# Memory.net
KiCad netlist of a schematic drawn in Altium Designer
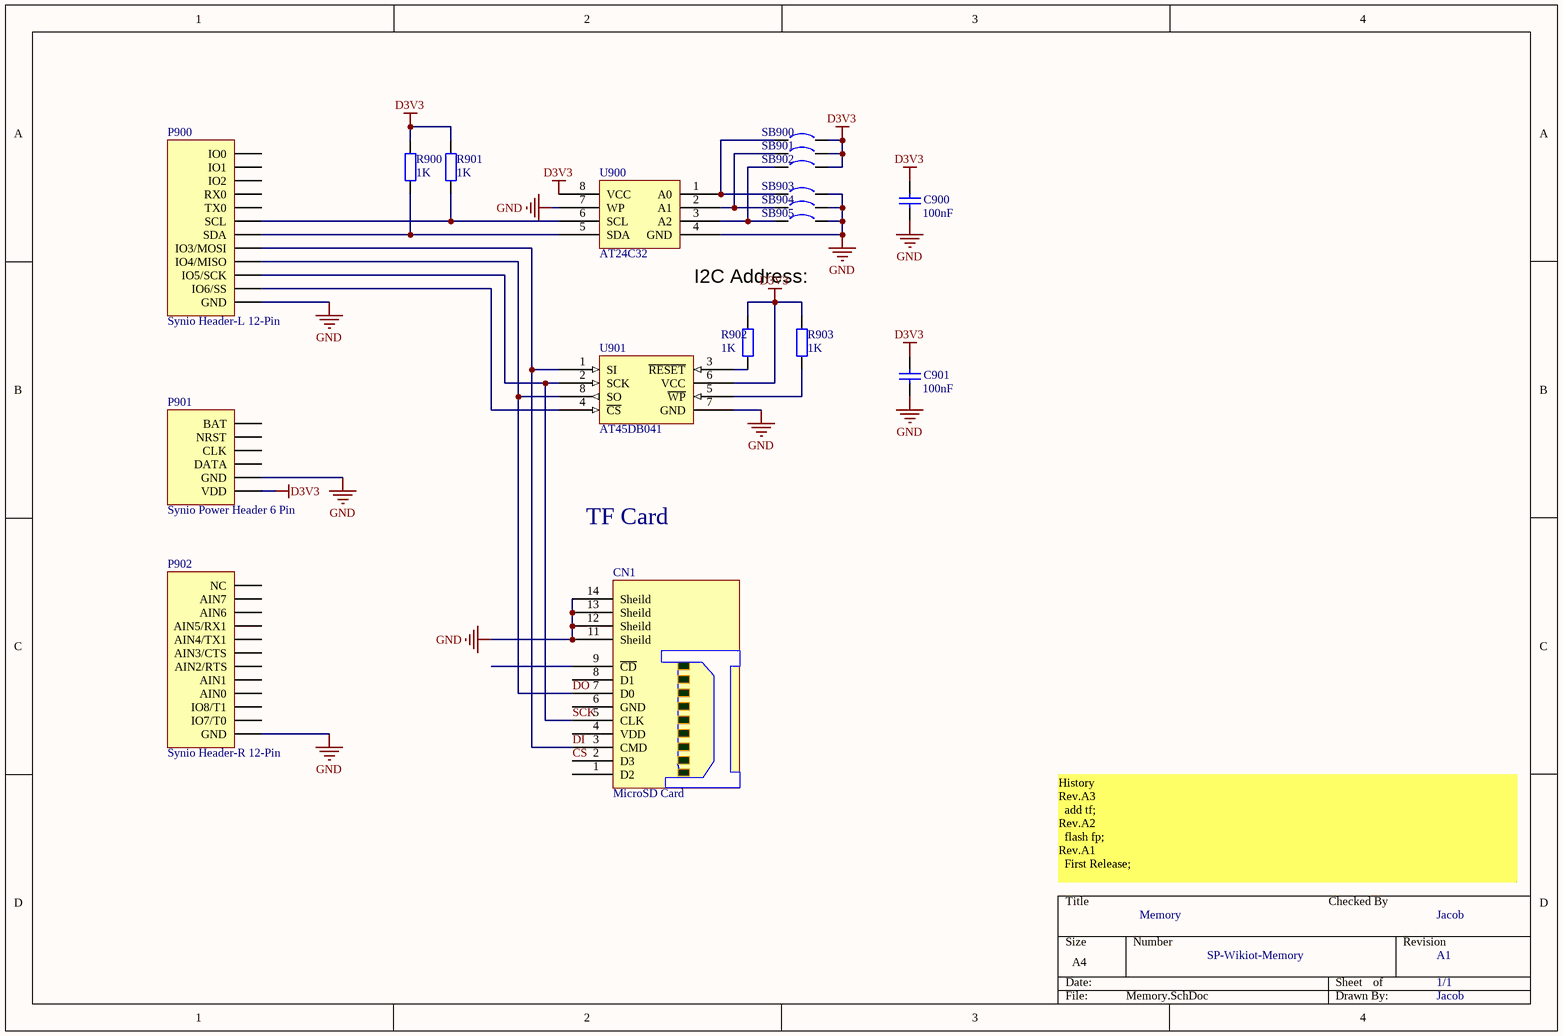
[diagram p0: Memory.SchDoc]

(export (version "E")
  (design (tool "Eeschema 10.0.6"))
  (components
    (comp (ref "C900")
      (value "100nF")
      (footprint "C0603L")
      (description "Capacitor")
      (fields (field (name "PUBLISHER") "Altium Limited"))
      (libsource (lib "Miscellaneous Devices") (part "Cap"))
    )
    (comp (ref "C901")
      (value "100nF")
      (footprint "C0603L")
      (description "Capacitor")
      (fields (field (name "PUBLISHER") "Altium Limited"))
      (libsource (lib "Miscellaneous Devices") (part "Cap"))
    )
    (comp (ref "CN1")
      (value "MicroSD Card")
      (footprint "MicroSD")
      (libsource (lib "Connector") (part "MicroSD Card"))
    )
    (comp (ref "P900")
      (value "Synio Header-L 12-Pin")
      (footprint "HDR1X12/2.54MM")
      (description "Synio Header-L, 12-Pin")
      (fields (field (name "PUBLISHER") "Altium Limited"))
      (libsource (lib "Connector") (part "Synio Header-L 12-Pin"))
    )
    (comp (ref "P901")
      (value "Synio Power Header 6 Pin")
      (footprint "HDR1X6/2.54MM")
      (libsource (lib "Connector") (part "Synio Power Header 6 Pin"))
    )
    (comp (ref "P902")
      (value "Synio Header-R 12-Pin")
      (footprint "HDR1X12/2.54MM")
      (description "Synio Header-R, 12-Pin")
      (fields (field (name "PUBLISHER") "Altium Limited"))
      (libsource (lib "Connector") (part "Synio Header-R 12-Pin"))
    )
    (comp (ref "R900")
      (value "1K")
      (footprint "R0603")
      (description "Resistor")
      (fields (field (name "PUBLISHER") "Altium Limited"))
      (libsource (lib "Miscellaneous Devices") (part "Res2"))
    )
    (comp (ref "R901")
      (value "1K")
      (footprint "R0603")
      (description "Resistor")
      (fields (field (name "PUBLISHER") "Altium Limited"))
      (libsource (lib "Miscellaneous Devices") (part "Res2"))
    )
    (comp (ref "R902")
      (value "1K")
      (footprint "R0603")
      (description "Resistor")
      (fields (field (name "PUBLISHER") "Altium Limited"))
      (libsource (lib "") (part "Res2_1"))
    )
    (comp (ref "R903")
      (value "1K")
      (footprint "R0603")
      (description "Resistor")
      (fields (field (name "PUBLISHER") "Altium Limited"))
      (libsource (lib "") (part "Res2_1"))
    )
    (comp (ref "SB900")
      (value "Circuit Breaker")
      (footprint "JP2_SMD")
      (fields (field (name "PUBLISHER") "Altium Limited"))
      (libsource (lib "Misc") (part "Circuit Breaker"))
    )
    (comp (ref "SB901")
      (value "Circuit Breaker")
      (footprint "JP2_SMD")
      (fields (field (name "PUBLISHER") "Altium Limited"))
      (libsource (lib "Misc") (part "Circuit Breaker"))
    )
    (comp (ref "SB902")
      (value "Circuit Breaker")
      (footprint "JP2_SMD")
      (fields (field (name "PUBLISHER") "Altium Limited"))
      (libsource (lib "Misc") (part "Circuit Breaker"))
    )
    (comp (ref "SB903")
      (value "Circuit Breaker")
      (footprint "JP2_SMD")
      (fields (field (name "PUBLISHER") "Altium Limited"))
      (libsource (lib "Misc") (part "Circuit Breaker"))
    )
    (comp (ref "SB904")
      (value "Circuit Breaker")
      (footprint "JP2_SMD")
      (fields (field (name "PUBLISHER") "Altium Limited"))
      (libsource (lib "Misc") (part "Circuit Breaker"))
    )
    (comp (ref "SB905")
      (value "Circuit Breaker")
      (footprint "JP2_SMD")
      (fields (field (name "PUBLISHER") "Altium Limited"))
      (libsource (lib "Misc") (part "Circuit Breaker"))
    )
    (comp (ref "U900")
      (value "AT24C32")
      (footprint "SO8W_M")
      (description "IIC EEPROM")
      (libsource (lib "Logic") (part "At24CXX"))
    )
    (comp (ref "U901")
      (value "AT45DB041")
      (footprint "SO8_N")
      (description "4M Serial Flash")
      (libsource (lib "Logic") (part "AT45DB041"))
    )
  )
  (nets
    (net (code "1") (name "/CS") (class "Default")
      (node (ref "CN1") (pin "2") (pinfunction "D3_2") (pintype "passive"))
    )
    (net (code "2") (name "/DI") (class "Default")
      (node (ref "CN1") (pin "3") (pinfunction "CMD_3") (pintype "passive"))
      (node (ref "P900") (pin "5") (pinfunction "IO3/MOSI_5") (pintype "passive"))
      (node (ref "U901") (pin "1") (pinfunction "SI_1") (pintype "input"))
    )
    (net (code "3") (name "/DO") (class "Default")
      (node (ref "CN1") (pin "7") (pinfunction "D0_7") (pintype "passive"))
      (node (ref "P900") (pin "4") (pinfunction "IO4/MISO_4") (pintype "passive"))
      (node (ref "U901") (pin "8") (pinfunction "SO_8") (pintype "output"))
    )
    (net (code "4") (name "/SCK") (class "Default")
      (node (ref "CN1") (pin "5") (pinfunction "CLK_5") (pintype "passive"))
      (node (ref "P900") (pin "3") (pinfunction "IO5/SCK_3") (pintype "passive"))
      (node (ref "U901") (pin "2") (pinfunction "SCK_2") (pintype "input"))
    )
    (net (code "5") (name "D3V3") (class "Default")
      (node (ref "C900") (pin "1") (pinfunction "1_1") (pintype "passive"))
      (node (ref "C901") (pin "1") (pinfunction "1_1") (pintype "passive"))
      (node (ref "P901") (pin "1") (pinfunction "VDD_1") (pintype "passive"))
      (node (ref "R900") (pin "2") (pinfunction "2_2") (pintype "passive"))
      (node (ref "R901") (pin "2") (pinfunction "2_2") (pintype "passive"))
      (node (ref "R902") (pin "1") (pinfunction "1_1") (pintype "passive"))
      (node (ref "R903") (pin "1") (pinfunction "1_1") (pintype "passive"))
      (node (ref "SB900") (pin "2") (pinfunction "2_2") (pintype "passive"))
      (node (ref "SB901") (pin "2") (pinfunction "2_2") (pintype "passive"))
      (node (ref "SB902") (pin "2") (pinfunction "2_2") (pintype "passive"))
      (node (ref "U900") (pin "8") (pinfunction "VCC_8") (pintype "passive"))
      (node (ref "U901") (pin "6") (pinfunction "VCC_6") (pintype "power_in"))
    )
    (net (code "6") (name "GND") (class "Default")
      (node (ref "C900") (pin "2") (pinfunction "2_2") (pintype "passive"))
      (node (ref "C901") (pin "2") (pinfunction "2_2") (pintype "passive"))
      (node (ref "CN1") (pin "11") (pinfunction "Sheild_11") (pintype "passive"))
      (node (ref "CN1") (pin "12") (pinfunction "Sheild_12") (pintype "passive"))
      (node (ref "CN1") (pin "13") (pinfunction "Sheild_13") (pintype "passive"))
      (node (ref "CN1") (pin "14") (pinfunction "Sheild_14") (pintype "passive"))
      (node (ref "P900") (pin "1") (pinfunction "GND_1") (pintype "passive"))
      (node (ref "P901") (pin "2") (pinfunction "GND_2") (pintype "passive"))
      (node (ref "P902") (pin "1") (pinfunction "GND_1") (pintype "passive"))
      (node (ref "SB903") (pin "2") (pinfunction "2_2") (pintype "passive"))
      (node (ref "SB904") (pin "2") (pinfunction "2_2") (pintype "passive"))
      (node (ref "SB905") (pin "2") (pinfunction "2_2") (pintype "passive"))
      (node (ref "U900") (pin "4") (pinfunction "GND_4") (pintype "passive"))
      (node (ref "U900") (pin "7") (pinfunction "WP_7") (pintype "passive"))
      (node (ref "U901") (pin "7") (pinfunction "GND_7") (pintype "power_in"))
    )
    (net (code "7") (name "Net-(P900-IO6{slash}SS)") (class "Default")
      (node (ref "P900") (pin "2") (pinfunction "IO6/SS_2") (pintype "passive"))
      (node (ref "U901") (pin "4") (pinfunction "~{CS}_4") (pintype "input"))
    )
    (net (code "8") (name "Net-(P900-SCL)") (class "Default")
      (node (ref "P900") (pin "7") (pinfunction "SCL_7") (pintype "passive"))
      (node (ref "R901") (pin "1") (pinfunction "1_1") (pintype "passive"))
      (node (ref "U900") (pin "6") (pinfunction "SCL_6") (pintype "passive"))
    )
    (net (code "9") (name "Net-(P900-SDA)") (class "Default")
      (node (ref "P900") (pin "6") (pinfunction "SDA_6") (pintype "passive"))
      (node (ref "R900") (pin "1") (pinfunction "1_1") (pintype "passive"))
      (node (ref "U900") (pin "5") (pinfunction "SDA_5") (pintype "passive"))
    )
    (net (code "10") (name "Net-(U900-A0)") (class "Default")
      (node (ref "SB900") (pin "1") (pinfunction "1_1") (pintype "passive"))
      (node (ref "SB903") (pin "1") (pinfunction "1_1") (pintype "passive"))
      (node (ref "U900") (pin "1") (pinfunction "A0_1") (pintype "passive"))
    )
    (net (code "11") (name "Net-(U900-A1)") (class "Default")
      (node (ref "SB901") (pin "1") (pinfunction "1_1") (pintype "passive"))
      (node (ref "SB904") (pin "1") (pinfunction "1_1") (pintype "passive"))
      (node (ref "U900") (pin "2") (pinfunction "A1_2") (pintype "passive"))
    )
    (net (code "12") (name "Net-(U900-A2)") (class "Default")
      (node (ref "SB902") (pin "1") (pinfunction "1_1") (pintype "passive"))
      (node (ref "SB905") (pin "1") (pinfunction "1_1") (pintype "passive"))
      (node (ref "U900") (pin "3") (pinfunction "A2_3") (pintype "passive"))
    )
    (net (code "13") (name "Net-(U901-~{RESET})") (class "Default")
      (node (ref "R902") (pin "2") (pinfunction "2_2") (pintype "passive"))
      (node (ref "U901") (pin "3") (pinfunction "~{RESET}_3") (pintype "input"))
    )
    (net (code "14") (name "Net-(U901-~{WP})") (class "Default")
      (node (ref "R903") (pin "2") (pinfunction "2_2") (pintype "passive"))
      (node (ref "U901") (pin "5") (pinfunction "~{WP}_5") (pintype "input"))
    )
    (net (code "15") (name "unconnected-(CN1-D1-Pad8)") (class "Default")
      (node (ref "CN1") (pin "8") (pinfunction "D1_8") (pintype "passive"))
    )
    (net (code "16") (name "unconnected-(CN1-D2-Pad1)") (class "Default")
      (node (ref "CN1") (pin "1") (pinfunction "D2_1") (pintype "passive"))
    )
    (net (code "17") (name "unconnected-(CN1-GND-Pad6)") (class "Default")
      (node (ref "CN1") (pin "6") (pinfunction "GND_6") (pintype "passive"))
    )
    (net (code "18") (name "unconnected-(CN1-VDD-Pad4)") (class "Default")
      (node (ref "CN1") (pin "4") (pinfunction "VDD_4") (pintype "passive"))
    )
    (net (code "19") (name "unconnected-(CN1-~{CD}-Pad9)") (class "Default")
      (node (ref "CN1") (pin "9") (pinfunction "~{CD}_9") (pintype "passive"))
    )
    (net (code "20") (name "unconnected-(P900-IO0-Pad12)") (class "Default")
      (node (ref "P900") (pin "12") (pinfunction "IO0_12") (pintype "passive"))
    )
    (net (code "21") (name "unconnected-(P900-IO1-Pad11)") (class "Default")
      (node (ref "P900") (pin "11") (pinfunction "IO1_11") (pintype "passive"))
    )
    (net (code "22") (name "unconnected-(P900-IO2-Pad10)") (class "Default")
      (node (ref "P900") (pin "10") (pinfunction "IO2_10") (pintype "passive"))
    )
    (net (code "23") (name "unconnected-(P900-RX0-Pad9)") (class "Default")
      (node (ref "P900") (pin "9") (pinfunction "RX0_9") (pintype "passive"))
    )
    (net (code "24") (name "unconnected-(P900-TX0-Pad8)") (class "Default")
      (node (ref "P900") (pin "8") (pinfunction "TX0_8") (pintype "passive"))
    )
    (net (code "25") (name "unconnected-(P901-BAT-Pad6)") (class "Default")
      (node (ref "P901") (pin "6") (pinfunction "BAT_6") (pintype "passive"))
    )
    (net (code "26") (name "unconnected-(P901-CLK-Pad4)") (class "Default")
      (node (ref "P901") (pin "4") (pinfunction "CLK_4") (pintype "passive"))
    )
    (net (code "27") (name "unconnected-(P901-DATA-Pad3)") (class "Default")
      (node (ref "P901") (pin "3") (pinfunction "DATA_3") (pintype "passive"))
    )
    (net (code "28") (name "unconnected-(P901-NRST-Pad5)") (class "Default")
      (node (ref "P901") (pin "5") (pinfunction "NRST_5") (pintype "passive"))
    )
    (net (code "29") (name "unconnected-(P902-AIN0-Pad4)") (class "Default")
      (node (ref "P902") (pin "4") (pinfunction "AIN0_4") (pintype "passive"))
    )
    (net (code "30") (name "unconnected-(P902-AIN1-Pad5)") (class "Default")
      (node (ref "P902") (pin "5") (pinfunction "AIN1_5") (pintype "passive"))
    )
    (net (code "31") (name "unconnected-(P902-AIN2{slash}RTS-Pad6)") (class "Default")
      (node (ref "P902") (pin "6") (pinfunction "AIN2/RTS_6") (pintype "passive"))
    )
    (net (code "32") (name "unconnected-(P902-AIN3{slash}CTS-Pad7)") (class "Default")
      (node (ref "P902") (pin "7") (pinfunction "AIN3/CTS_7") (pintype "passive"))
    )
    (net (code "33") (name "unconnected-(P902-AIN4{slash}TX1-Pad8)") (class "Default")
      (node (ref "P902") (pin "8") (pinfunction "AIN4/TX1_8") (pintype "passive"))
    )
    (net (code "34") (name "unconnected-(P902-AIN5{slash}RX1-Pad9)") (class "Default")
      (node (ref "P902") (pin "9") (pinfunction "AIN5/RX1_9") (pintype "passive"))
    )
    (net (code "35") (name "unconnected-(P902-AIN6-Pad10)") (class "Default")
      (node (ref "P902") (pin "10") (pinfunction "AIN6_10") (pintype "passive"))
    )
    (net (code "36") (name "unconnected-(P902-AIN7-Pad11)") (class "Default")
      (node (ref "P902") (pin "11") (pinfunction "AIN7_11") (pintype "passive"))
    )
    (net (code "37") (name "unconnected-(P902-IO7{slash}T0-Pad2)") (class "Default")
      (node (ref "P902") (pin "2") (pinfunction "IO7/T0_2") (pintype "passive"))
    )
    (net (code "38") (name "unconnected-(P902-IO8{slash}T1-Pad3)") (class "Default")
      (node (ref "P902") (pin "3") (pinfunction "IO8/T1_3") (pintype "passive"))
    )
    (net (code "39") (name "unconnected-(P902-NC-Pad12)") (class "Default")
      (node (ref "P902") (pin "12") (pinfunction "NC_12") (pintype "passive"))
    )
  )
)
